# tracker03-07.net
KiCad netlist of a schematic drawn in EAGLE
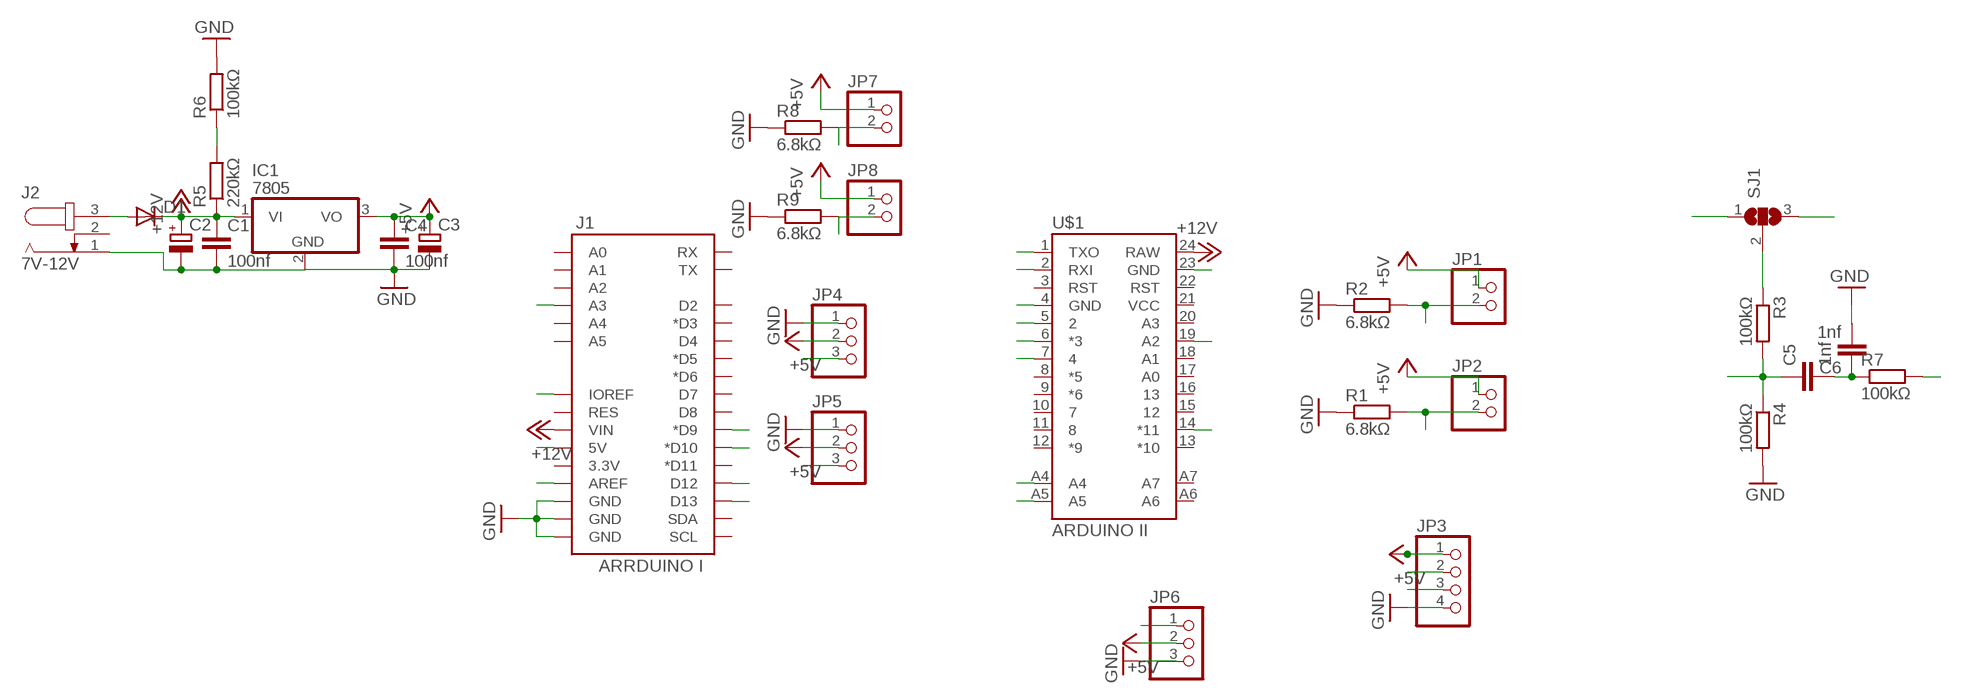
[diagram p0: schematic, sheet 1]

(export (version "E")
  (design (tool "Eeschema 10.0.6"))
  (components
    (comp (ref "C1")
      (value "100nf")
      (footprint "eagle-import:C050-025X075")
      (libsource (lib "eagle-import") (part "C-EU050-025X075"))
    )
    (comp (ref "C2")
      (value "CPOL-EUE3.5-8")
      (footprint "eagle-import:E3,5-8")
      (libsource (lib "eagle-import") (part "CPOL-EUE3.5-8"))
    )
    (comp (ref "C3")
      (value "CPOL-EUE2.5-5")
      (footprint "eagle-import:E2,5-5")
      (libsource (lib "eagle-import") (part "CPOL-EUE2.5-5"))
    )
    (comp (ref "C4")
      (value "100nf")
      (footprint "eagle-import:C050-025X075")
      (libsource (lib "eagle-import") (part "C-EU050-025X075"))
    )
    (comp (ref "C5")
      (value "1nf")
      (footprint "eagle-import:C050-025X075")
      (libsource (lib "eagle-import") (part "C-EU050-025X075"))
    )
    (comp (ref "C6")
      (value "1nf")
      (footprint "eagle-import:C050-025X075")
      (libsource (lib "eagle-import") (part "C-EU050-025X075"))
    )
    (comp (ref "D1")
      (value "1N4004")
      (footprint "eagle-import:DO41-10")
      (libsource (lib "eagle-import") (part "1N4004"))
    )
    (comp (ref "IC1")
      (value "7805")
      (footprint "eagle-import:TO220V")
      (libsource (lib "eagle-import") (part "78TV05"))
    )
    (comp (ref "J1")
      (value "ARRDUINO I")
      (footprint "eagle-import:UNO_R3_SHIELD_NOLABELS")
      (libsource (lib "eagle-import") (part "ARDUINO_R3_SHIELDNOLABELS"))
    )
    (comp (ref "J2")
      (value "7V-12V")
      (footprint "eagle-import:SPC4077")
      (libsource (lib "eagle-import") (part "JACK-PLUG0"))
    )
    (comp (ref "JP1")
      (value "PINHD-1X2")
      (footprint "eagle-import:1X02")
      (libsource (lib "eagle-import") (part "PINHD-1X2"))
    )
    (comp (ref "JP2")
      (value "PINHD-1X2")
      (footprint "eagle-import:1X02")
      (libsource (lib "eagle-import") (part "PINHD-1X2"))
    )
    (comp (ref "JP3")
      (value "PINHD-1X4")
      (footprint "eagle-import:1X04")
      (libsource (lib "eagle-import") (part "PINHD-1X4"))
    )
    (comp (ref "JP4")
      (value "PINHD-1X3")
      (footprint "eagle-import:1X03")
      (libsource (lib "eagle-import") (part "PINHD-1X3"))
    )
    (comp (ref "JP5")
      (value "PINHD-1X3")
      (footprint "eagle-import:1X03")
      (libsource (lib "eagle-import") (part "PINHD-1X3"))
    )
    (comp (ref "JP6")
      (value "PINHD-1X3")
      (footprint "eagle-import:1X03")
      (libsource (lib "eagle-import") (part "PINHD-1X3"))
    )
    (comp (ref "JP7")
      (value "PINHD-1X2")
      (footprint "eagle-import:1X02")
      (libsource (lib "eagle-import") (part "PINHD-1X2"))
    )
    (comp (ref "JP8")
      (value "PINHD-1X2")
      (footprint "eagle-import:1X02")
      (libsource (lib "eagle-import") (part "PINHD-1X2"))
    )
    (comp (ref "R1")
      (value "6.8kΩ")
      (footprint "eagle-import:0204V")
      (libsource (lib "eagle-import") (part "R-EU_0204/2V"))
    )
    (comp (ref "R2")
      (value "6.8kΩ")
      (footprint "eagle-import:0204V")
      (libsource (lib "eagle-import") (part "R-EU_0204/2V"))
    )
    (comp (ref "R3")
      (value "100kΩ")
      (footprint "eagle-import:0204V")
      (libsource (lib "eagle-import") (part "R-EU_0204/2V"))
    )
    (comp (ref "R4")
      (value "100kΩ")
      (footprint "eagle-import:0204V")
      (libsource (lib "eagle-import") (part "R-EU_0204/2V"))
    )
    (comp (ref "R5")
      (value "220kΩ")
      (footprint "eagle-import:0204V")
      (libsource (lib "eagle-import") (part "R-EU_0204/2V"))
    )
    (comp (ref "R6")
      (value "100kΩ")
      (footprint "eagle-import:0204V")
      (libsource (lib "eagle-import") (part "R-EU_0204/2V"))
    )
    (comp (ref "R7")
      (value "100kΩ")
      (footprint "eagle-import:0204V")
      (libsource (lib "eagle-import") (part "R-EU_0204/2V"))
    )
    (comp (ref "R8")
      (value "6.8kΩ")
      (footprint "eagle-import:0204V")
      (libsource (lib "eagle-import") (part "R-EU_0204/2V"))
    )
    (comp (ref "R9")
      (value "6.8kΩ")
      (footprint "eagle-import:0204V")
      (libsource (lib "eagle-import") (part "R-EU_0204/2V"))
    )
    (comp (ref "SJ1")
      (value "SJ2W")
      (footprint "eagle-import:SJ_2")
      (libsource (lib "eagle-import") (part "SJ2W"))
    )
    (comp (ref "U$1")
      (value "ARDUINO II")
      (footprint "eagle-import:ARDUINO_PRO_MINI")
      (libsource (lib "eagle-import") (part "ARDUINO_PRO_MINI"))
    )
  )
  (nets
    (net (code "1") (name "+5V") (class "Default")
      (node (ref "C3") (pin "+") (pinfunction "+_+") (pintype "passive"))
      (node (ref "C4") (pin "1") (pinfunction "1_1") (pintype "passive"))
      (node (ref "IC1") (pin "3") (pinfunction "VO_3") (pintype "passive"))
      (node (ref "JP1") (pin "1") (pinfunction "1_1") (pintype "passive"))
      (node (ref "JP2") (pin "1") (pinfunction "1_1") (pintype "passive"))
      (node (ref "JP3") (pin "1") (pinfunction "1_1") (pintype "passive"))
      (node (ref "JP4") (pin "2") (pinfunction "2_2") (pintype "passive"))
      (node (ref "JP5") (pin "2") (pinfunction "2_2") (pintype "passive"))
      (node (ref "JP6") (pin "2") (pinfunction "2_2") (pintype "passive"))
      (node (ref "JP7") (pin "1") (pinfunction "1_1") (pintype "passive"))
      (node (ref "JP8") (pin "1") (pinfunction "1_1") (pintype "passive"))
    )
    (net (code "2") (name "+12V") (class "Default")
      (node (ref "C1") (pin "1") (pinfunction "1_1") (pintype "passive"))
      (node (ref "C2") (pin "+") (pinfunction "+_+") (pintype "passive"))
      (node (ref "D1") (pin "C") (pinfunction "C_C") (pintype "passive"))
      (node (ref "IC1") (pin "1") (pinfunction "VI_1") (pintype "input"))
      (node (ref "J1") (pin "VIN") (pinfunction "VIN_VIN") (pintype "bidirectional"))
      (node (ref "R5") (pin "1") (pinfunction "1_1") (pintype "passive"))
      (node (ref "U$1") (pin "24") (pinfunction "RAW_24") (pintype "bidirectional"))
    )
    (net (code "3") (name "/5VA") (class "Default")
      (node (ref "J1") (pin "5V") (pinfunction "5V_5V") (pintype "bidirectional"))
      (node (ref "SJ1") (pin "3") (pinfunction "3_3") (pintype "passive"))
    )
    (net (code "4") (name "/A2") (class "Default")
      (node (ref "R5") (pin "2") (pinfunction "2_2") (pintype "passive"))
      (node (ref "R6") (pin "1") (pinfunction "1_1") (pintype "passive"))
      (node (ref "U$1") (pin "19") (pinfunction "A2_19") (pintype "bidirectional"))
    )
    (net (code "5") (name "/A3") (class "Default")
      (node (ref "C5") (pin "1") (pinfunction "1_1") (pintype "passive"))
      (node (ref "J1") (pin "A3") (pinfunction "A3_A3") (pintype "bidirectional"))
      (node (ref "R3") (pin "2") (pinfunction "2_2") (pintype "passive"))
      (node (ref "R4") (pin "1") (pinfunction "1_1") (pintype "passive"))
    )
    (net (code "6") (name "/A4") (class "Default")
      (node (ref "JP3") (pin "2") (pinfunction "2_2") (pintype "passive"))
      (node (ref "U$1") (pin "A4") (pinfunction "A4_A4") (pintype "bidirectional"))
    )
    (net (code "7") (name "/A5") (class "Default")
      (node (ref "JP3") (pin "3") (pinfunction "3_3") (pintype "passive"))
      (node (ref "U$1") (pin "A5") (pinfunction "A5_A5") (pintype "bidirectional"))
    )
    (net (code "8") (name "/AREF") (class "Default")
      (node (ref "J1") (pin "AREF") (pinfunction "AREF_AREF") (pintype "bidirectional"))
      (node (ref "SJ1") (pin "1") (pinfunction "1_1") (pintype "passive"))
    )
    (net (code "9") (name "/D2") (class "Default")
      (node (ref "JP1") (pin "2") (pinfunction "2_2") (pintype "passive"))
      (node (ref "R2") (pin "2") (pinfunction "2_2") (pintype "passive"))
      (node (ref "U$1") (pin "5") (pinfunction "2_5") (pintype "bidirectional"))
    )
    (net (code "10") (name "/D4") (class "Default")
      (node (ref "JP2") (pin "2") (pinfunction "2_2") (pintype "passive"))
      (node (ref "R1") (pin "2") (pinfunction "2_2") (pintype "passive"))
      (node (ref "U$1") (pin "7") (pinfunction "4_7") (pintype "bidirectional"))
    )
    (net (code "11") (name "/D9") (class "Default")
      (node (ref "J1") (pin "D9") (pinfunction "*D9_D9") (pintype "bidirectional"))
      (node (ref "JP4") (pin "3") (pinfunction "3_3") (pintype "passive"))
    )
    (net (code "12") (name "/D10") (class "Default")
      (node (ref "J1") (pin "D10") (pinfunction "*D10_D10") (pintype "bidirectional"))
      (node (ref "JP5") (pin "3") (pinfunction "3_3") (pintype "passive"))
    )
    (net (code "13") (name "/D11") (class "Default")
      (node (ref "JP6") (pin "1") (pinfunction "1_1") (pintype "passive"))
      (node (ref "U$1") (pin "14") (pinfunction "*11_14") (pintype "bidirectional"))
    )
    (net (code "14") (name "/D12") (class "Default")
      (node (ref "J1") (pin "D12") (pinfunction "D12_D12") (pintype "bidirectional"))
      (node (ref "JP7") (pin "2") (pinfunction "2_2") (pintype "passive"))
      (node (ref "R8") (pin "2") (pinfunction "2_2") (pintype "passive"))
    )
    (net (code "15") (name "/D13") (class "Default")
      (node (ref "J1") (pin "D13") (pinfunction "D13_D13") (pintype "bidirectional"))
      (node (ref "JP8") (pin "2") (pinfunction "2_2") (pintype "passive"))
      (node (ref "R9") (pin "2") (pinfunction "2_2") (pintype "passive"))
    )
    (net (code "16") (name "GND") (class "Default")
      (node (ref "C1") (pin "2") (pinfunction "2_2") (pintype "passive"))
      (node (ref "C2") (pin "-") (pinfunction "-_-") (pintype "passive"))
      (node (ref "C3") (pin "-") (pinfunction "-_-") (pintype "passive"))
      (node (ref "C4") (pin "2") (pinfunction "2_2") (pintype "passive"))
      (node (ref "C6") (pin "2") (pinfunction "2_2") (pintype "passive"))
      (node (ref "IC1") (pin "2") (pinfunction "GND_2") (pintype "passive"))
      (node (ref "J1") (pin "GND@0") (pinfunction "GND_GND@0") (pintype "bidirectional"))
      (node (ref "J1") (pin "GND@1") (pinfunction "GND_GND@1") (pintype "bidirectional"))
      (node (ref "J1") (pin "GND@2") (pinfunction "GND_GND@2") (pintype "bidirectional"))
      (node (ref "J2") (pin "1") (pinfunction "1_1") (pintype "passive"))
      (node (ref "JP3") (pin "4") (pinfunction "4_4") (pintype "passive"))
      (node (ref "JP4") (pin "1") (pinfunction "1_1") (pintype "passive"))
      (node (ref "JP5") (pin "1") (pinfunction "1_1") (pintype "passive"))
      (node (ref "JP6") (pin "3") (pinfunction "3_3") (pintype "passive"))
      (node (ref "R1") (pin "1") (pinfunction "1_1") (pintype "passive"))
      (node (ref "R2") (pin "1") (pinfunction "1_1") (pintype "passive"))
      (node (ref "R4") (pin "2") (pinfunction "2_2") (pintype "passive"))
      (node (ref "R6") (pin "2") (pinfunction "2_2") (pintype "passive"))
      (node (ref "R8") (pin "1") (pinfunction "1_1") (pintype "passive"))
      (node (ref "R9") (pin "1") (pinfunction "1_1") (pintype "passive"))
      (node (ref "U$1") (pin "23") (pinfunction "GND_23") (pintype "bidirectional"))
      (node (ref "U$1") (pin "4") (pinfunction "GND_4") (pintype "bidirectional"))
    )
    (net (code "17") (name "Net-(C5-Pad2)") (class "Default")
      (node (ref "C5") (pin "2") (pinfunction "2_2") (pintype "passive"))
      (node (ref "C6") (pin "1") (pinfunction "1_1") (pintype "passive"))
      (node (ref "R7") (pin "1") (pinfunction "1_1") (pintype "passive"))
    )
    (net (code "18") (name "Net-(D1-PadA)") (class "Default")
      (node (ref "D1") (pin "A") (pinfunction "A_A") (pintype "passive"))
      (node (ref "J2") (pin "3") (pinfunction "3_3") (pintype "passive"))
    )
    (net (code "19") (name "Net-(R3-Pad1)") (class "Default")
      (node (ref "R3") (pin "1") (pinfunction "1_1") (pintype "passive"))
      (node (ref "SJ1") (pin "2") (pinfunction "2_2") (pintype "passive"))
    )
    (net (code "20") (name "unconnected-(J1-*D3-PadD3)") (class "Default")
      (node (ref "J1") (pin "D3") (pinfunction "*D3_D3") (pintype "bidirectional"))
    )
    (net (code "21") (name "unconnected-(J1-*D5-PadD5)") (class "Default")
      (node (ref "J1") (pin "D5") (pinfunction "*D5_D5") (pintype "bidirectional"))
    )
    (net (code "22") (name "unconnected-(J1-*D6-PadD6)") (class "Default")
      (node (ref "J1") (pin "D6") (pinfunction "*D6_D6") (pintype "bidirectional"))
    )
    (net (code "23") (name "unconnected-(J1-*D11-PadD11)") (class "Default")
      (node (ref "J1") (pin "D11") (pinfunction "*D11_D11") (pintype "bidirectional"))
    )
    (net (code "24") (name "unconnected-(J1-Pad3.3V)") (class "Default")
      (node (ref "J1") (pin "3.3V") (pinfunction "3.3V_3.3V") (pintype "bidirectional"))
    )
    (net (code "25") (name "unconnected-(J1-PadA0)") (class "Default")
      (node (ref "J1") (pin "A0") (pinfunction "A0_A0") (pintype "bidirectional"))
    )
    (net (code "26") (name "unconnected-(J1-PadA1)") (class "Default")
      (node (ref "J1") (pin "A1") (pinfunction "A1_A1") (pintype "bidirectional"))
    )
    (net (code "27") (name "unconnected-(J1-PadA2)") (class "Default")
      (node (ref "J1") (pin "A2") (pinfunction "A2_A2") (pintype "bidirectional"))
    )
    (net (code "28") (name "unconnected-(J1-PadA4)") (class "Default")
      (node (ref "J1") (pin "A4") (pinfunction "A4_A4") (pintype "bidirectional"))
    )
    (net (code "29") (name "unconnected-(J1-PadA5)") (class "Default")
      (node (ref "J1") (pin "A5") (pinfunction "A5_A5") (pintype "bidirectional"))
    )
    (net (code "30") (name "unconnected-(J1-PadD2)") (class "Default")
      (node (ref "J1") (pin "D2") (pinfunction "D2_D2") (pintype "bidirectional"))
    )
    (net (code "31") (name "unconnected-(J1-PadD4)") (class "Default")
      (node (ref "J1") (pin "D4") (pinfunction "D4_D4") (pintype "bidirectional"))
    )
    (net (code "32") (name "unconnected-(J1-PadD7)") (class "Default")
      (node (ref "J1") (pin "D7") (pinfunction "D7_D7") (pintype "bidirectional"))
    )
    (net (code "33") (name "unconnected-(J1-PadD8)") (class "Default")
      (node (ref "J1") (pin "D8") (pinfunction "D8_D8") (pintype "bidirectional"))
    )
    (net (code "34") (name "unconnected-(J1-PadIOREF)") (class "Default")
      (node (ref "J1") (pin "IOREF") (pinfunction "IOREF_IOREF") (pintype "bidirectional"))
    )
    (net (code "35") (name "unconnected-(J1-PadRES)") (class "Default")
      (node (ref "J1") (pin "RES") (pinfunction "RES_RES") (pintype "bidirectional"))
    )
    (net (code "36") (name "unconnected-(J1-PadRX)") (class "Default")
      (node (ref "J1") (pin "RX") (pinfunction "RX_RX") (pintype "bidirectional"))
    )
    (net (code "37") (name "unconnected-(J1-PadSCL)") (class "Default")
      (node (ref "J1") (pin "SCL") (pinfunction "SCL_SCL") (pintype "bidirectional"))
    )
    (net (code "38") (name "unconnected-(J1-PadSDA)") (class "Default")
      (node (ref "J1") (pin "SDA") (pinfunction "SDA_SDA") (pintype "bidirectional"))
    )
    (net (code "39") (name "unconnected-(J1-PadTX)") (class "Default")
      (node (ref "J1") (pin "TX") (pinfunction "TX_TX") (pintype "bidirectional"))
    )
    (net (code "40") (name "unconnected-(J2-Pad2)") (class "Default")
      (node (ref "J2") (pin "2") (pinfunction "2_2") (pintype "passive"))
    )
    (net (code "41") (name "unconnected-(R7-Pad2)") (class "Default")
      (node (ref "R7") (pin "2") (pinfunction "2_2") (pintype "passive"))
    )
    (net (code "42") (name "unconnected-(U$1-*3-Pad6)") (class "Default")
      (node (ref "U$1") (pin "6") (pinfunction "*3_6") (pintype "bidirectional"))
    )
    (net (code "43") (name "unconnected-(U$1-*5-Pad8)") (class "Default")
      (node (ref "U$1") (pin "8") (pinfunction "*5_8") (pintype "bidirectional"))
    )
    (net (code "44") (name "unconnected-(U$1-*6-Pad9)") (class "Default")
      (node (ref "U$1") (pin "9") (pinfunction "*6_9") (pintype "bidirectional"))
    )
    (net (code "45") (name "unconnected-(U$1-*9-Pad12)") (class "Default")
      (node (ref "U$1") (pin "12") (pinfunction "*9_12") (pintype "bidirectional"))
    )
    (net (code "46") (name "unconnected-(U$1-*10-Pad13)") (class "Default")
      (node (ref "U$1") (pin "13") (pinfunction "*10_13") (pintype "bidirectional"))
    )
    (net (code "47") (name "unconnected-(U$1-7-Pad10)") (class "Default")
      (node (ref "U$1") (pin "10") (pinfunction "7_10") (pintype "bidirectional"))
    )
    (net (code "48") (name "unconnected-(U$1-8-Pad11)") (class "Default")
      (node (ref "U$1") (pin "11") (pinfunction "8_11") (pintype "bidirectional"))
    )
    (net (code "49") (name "unconnected-(U$1-12-Pad15)") (class "Default")
      (node (ref "U$1") (pin "15") (pinfunction "12_15") (pintype "bidirectional"))
    )
    (net (code "50") (name "unconnected-(U$1-13-Pad16)") (class "Default")
      (node (ref "U$1") (pin "16") (pinfunction "13_16") (pintype "bidirectional"))
    )
    (net (code "51") (name "unconnected-(U$1-A0-Pad17)") (class "Default")
      (node (ref "U$1") (pin "17") (pinfunction "A0_17") (pintype "bidirectional"))
    )
    (net (code "52") (name "unconnected-(U$1-A1-Pad18)") (class "Default")
      (node (ref "U$1") (pin "18") (pinfunction "A1_18") (pintype "bidirectional"))
    )
    (net (code "53") (name "unconnected-(U$1-A3-Pad20)") (class "Default")
      (node (ref "U$1") (pin "20") (pinfunction "A3_20") (pintype "bidirectional"))
    )
    (net (code "54") (name "unconnected-(U$1-PadA6)") (class "Default")
      (node (ref "U$1") (pin "A6") (pinfunction "A6_A6") (pintype "bidirectional"))
    )
    (net (code "55") (name "unconnected-(U$1-PadA7)") (class "Default")
      (node (ref "U$1") (pin "A7") (pinfunction "A7_A7") (pintype "bidirectional"))
    )
    (net (code "56") (name "unconnected-(U$1-RST-Pad3)") (class "Default")
      (node (ref "U$1") (pin "3") (pinfunction "RST_3") (pintype "bidirectional"))
    )
    (net (code "57") (name "unconnected-(U$1-RST-Pad22)") (class "Default")
      (node (ref "U$1") (pin "22") (pinfunction "RST_22") (pintype "bidirectional"))
    )
    (net (code "58") (name "unconnected-(U$1-RXI-Pad2)") (class "Default")
      (node (ref "U$1") (pin "2") (pinfunction "RXI_2") (pintype "bidirectional"))
    )
    (net (code "59") (name "unconnected-(U$1-TXO-Pad1)") (class "Default")
      (node (ref "U$1") (pin "1") (pinfunction "TXO_1") (pintype "bidirectional"))
    )
    (net (code "60") (name "unconnected-(U$1-VCC-Pad21)") (class "Default")
      (node (ref "U$1") (pin "21") (pinfunction "VCC_21") (pintype "bidirectional"))
    )
  )
)
